# Shock_Clock.net
KiCad netlist of a schematic drawn in EAGLE
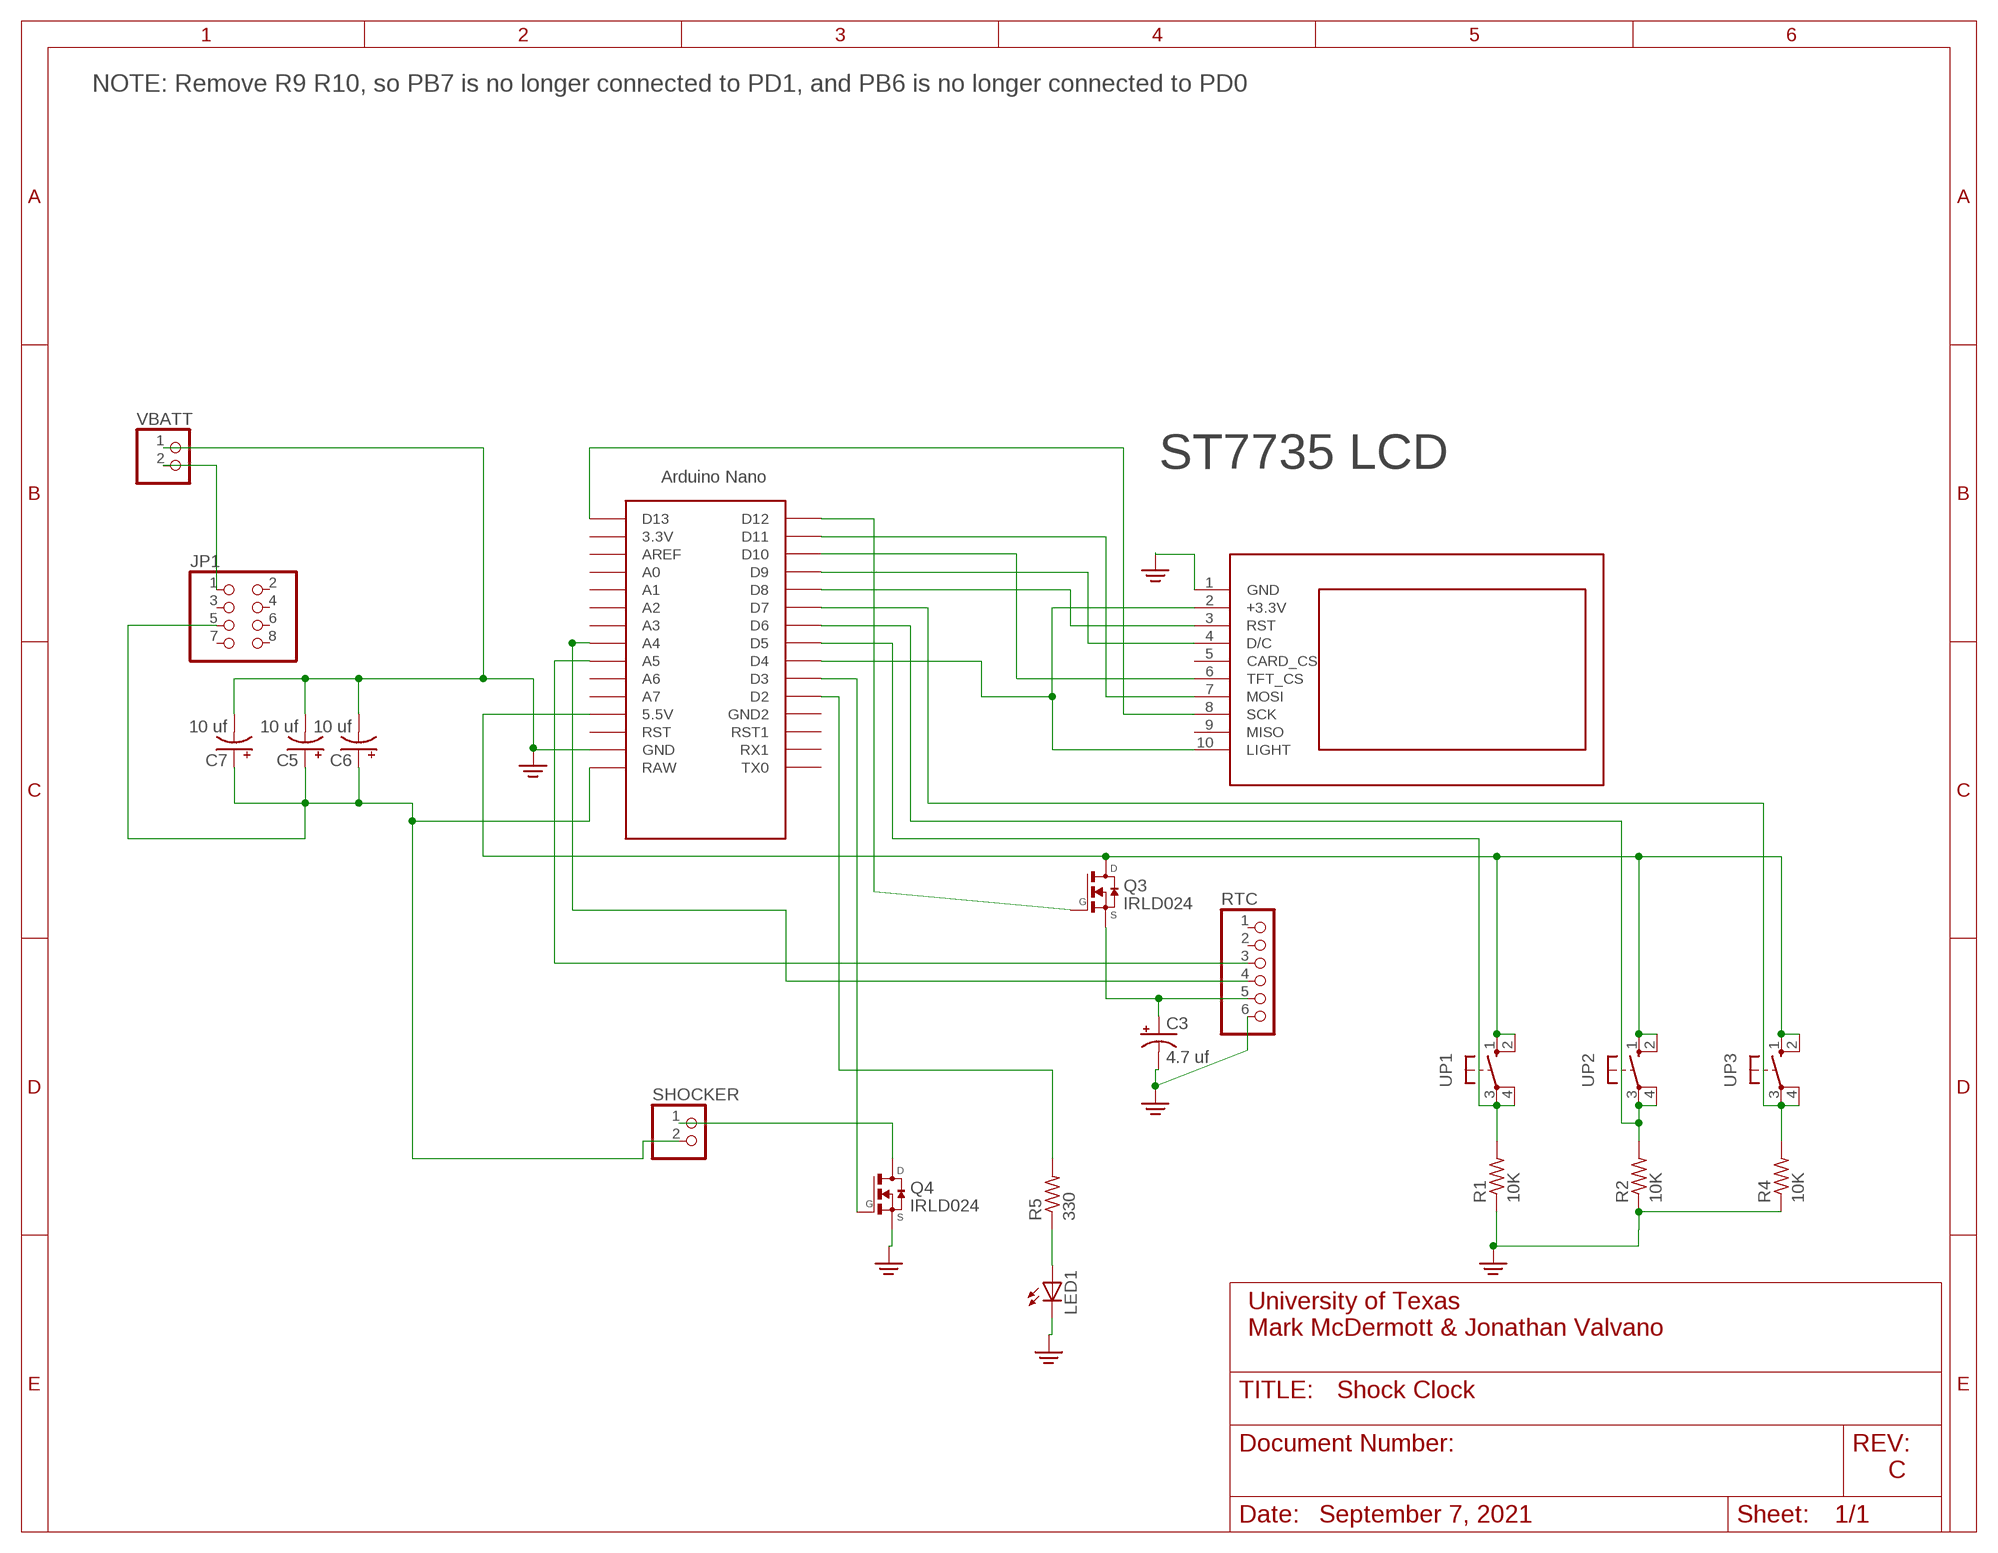
[diagram p0: schematic, sheet 1]

(export (version "E")
  (design (tool "Eeschema 10.0.6"))
  (components
    (comp (ref "C3")
      (value "4.7 uf")
      (footprint "eagle-import:CAP200MILPOLARIZED")
      (libsource (lib "eagle-import") (part "CAPACITOR_POLARIZEDE5-6"))
    )
    (comp (ref "C5")
      (value "10 uf")
      (footprint "eagle-import:CAP200MILPOLARIZED")
      (libsource (lib "eagle-import") (part "CAPACITOR_POLARIZEDE5-6"))
    )
    (comp (ref "C6")
      (value "10 uf")
      (footprint "eagle-import:CAP200MILPOLARIZED")
      (libsource (lib "eagle-import") (part "CAPACITOR_POLARIZEDE5-6"))
    )
    (comp (ref "C7")
      (value "10 uf")
      (footprint "eagle-import:CAP200MILPOLARIZED")
      (libsource (lib "eagle-import") (part "CAPACITOR_POLARIZEDE5-6"))
    )
    (comp (ref "JP1")
      (value "PINHD-2X4")
      (footprint "eagle-import:2X04")
      (libsource (lib "eagle-import") (part "PINHD-2X4"))
    )
    (comp (ref "LED1")
      (value "LED3MM")
      (footprint "eagle-import:LED3MM")
      (libsource (lib "eagle-import") (part "LED3MM"))
    )
    (comp (ref "Q3")
      (value "IRLD024")
      (footprint "eagle-import:IRLD024")
      (libsource (lib "eagle-import") (part "IRLD024"))
    )
    (comp (ref "Q4")
      (value "IRLD024")
      (footprint "eagle-import:IRLD024")
      (libsource (lib "eagle-import") (part "IRLD024"))
    )
    (comp (ref "R1")
      (value "10K")
      (footprint "eagle-import:RES300MIL")
      (libsource (lib "eagle-import") (part "RESISTOR0204/7"))
    )
    (comp (ref "R2")
      (value "10K")
      (footprint "eagle-import:RES300MIL")
      (libsource (lib "eagle-import") (part "RESISTOR0204/7"))
    )
    (comp (ref "R4")
      (value "10K")
      (footprint "eagle-import:RES300MIL")
      (libsource (lib "eagle-import") (part "RESISTOR0204/7"))
    )
    (comp (ref "R5")
      (value "330")
      (footprint "eagle-import:RES300MIL")
      (libsource (lib "eagle-import") (part "RESISTOR0204/7"))
    )
    (comp (ref "RTC")
      (value "PINHD-1X6")
      (footprint "eagle-import:1X06")
      (libsource (lib "eagle-import") (part "PINHD-1X6"))
    )
    (comp (ref "SHOCKER")
      (value "PINHD-1X2")
      (footprint "eagle-import:1X02")
      (libsource (lib "eagle-import") (part "PINHD-1X2"))
    )
    (comp (ref "U$3")
      (value "ST7735")
      (footprint "eagle-import:ST7735")
      (libsource (lib "eagle-import") (part "ST7735"))
    )
    (comp (ref "U$5")
      (value "NANO")
      (footprint "eagle-import:NANO")
      (libsource (lib "eagle-import") (part "NANO"))
    )
    (comp (ref "UP1")
      (value "B3F-1052")
      (footprint "eagle-import:B3F-10XX")
      (fields (field (name "MPN") "B3F-1000"))
      (libsource (lib "eagle-import") (part "B3F-1052"))
    )
    (comp (ref "UP2")
      (value "B3F-1052")
      (footprint "eagle-import:B3F-10XX")
      (fields (field (name "MPN") "B3F-1000"))
      (libsource (lib "eagle-import") (part "B3F-1052"))
    )
    (comp (ref "UP3")
      (value "B3F-1052")
      (footprint "eagle-import:B3F-10XX")
      (fields (field (name "MPN") "B3F-1000"))
      (libsource (lib "eagle-import") (part "B3F-1052"))
    )
    (comp (ref "VBATT")
      (value "PINHD-1X2")
      (footprint "eagle-import:1X02")
      (libsource (lib "eagle-import") (part "PINHD-1X2"))
    )
  )
  (nets
    (net (code "1") (name "GND") (class "Default")
      (node (ref "C3") (pin "-") (pinfunction "-_-") (pintype "passive"))
      (node (ref "C5") (pin "-") (pinfunction "-_-") (pintype "passive"))
      (node (ref "C6") (pin "-") (pinfunction "-_-") (pintype "passive"))
      (node (ref "C7") (pin "-") (pinfunction "-_-") (pintype "passive"))
      (node (ref "LED1") (pin "K") (pinfunction "C_K") (pintype "passive"))
      (node (ref "Q4") (pin "P$4") (pinfunction "S_P$4") (pintype "passive"))
      (node (ref "R1") (pin "1") (pinfunction "1_1") (pintype "passive"))
      (node (ref "R2") (pin "1") (pinfunction "1_1") (pintype "passive"))
      (node (ref "R4") (pin "1") (pinfunction "1_1") (pintype "passive"))
      (node (ref "RTC") (pin "6") (pinfunction "6_6") (pintype "passive"))
      (node (ref "U$3") (pin "1") (pinfunction "GND_1") (pintype "bidirectional"))
      (node (ref "U$5") (pin "GND") (pinfunction "GND_GND") (pintype "bidirectional"))
      (node (ref "VBATT") (pin "1") (pinfunction "1_1") (pintype "passive"))
    )
    (net (code "2") (name "Net-(C5-Pad+)") (class "Default")
      (node (ref "C5") (pin "+") (pinfunction "+_+") (pintype "passive"))
      (node (ref "C6") (pin "+") (pinfunction "+_+") (pintype "passive"))
      (node (ref "C7") (pin "+") (pinfunction "+_+") (pintype "passive"))
      (node (ref "JP1") (pin "5") (pinfunction "5_5") (pintype "passive"))
      (node (ref "SHOCKER") (pin "2") (pinfunction "2_2") (pintype "passive"))
      (node (ref "U$5") (pin "RAW") (pinfunction "RAW_RAW") (pintype "bidirectional"))
    )
    (net (code "3") (name "Net-(JP1-Pad1)") (class "Default")
      (node (ref "JP1") (pin "1") (pinfunction "1_1") (pintype "passive"))
      (node (ref "VBATT") (pin "2") (pinfunction "2_2") (pintype "passive"))
    )
    (net (code "4") (name "Net-(LED1-PadA)") (class "Default")
      (node (ref "LED1") (pin "A") (pinfunction "A_A") (pintype "passive"))
      (node (ref "R5") (pin "1") (pinfunction "1_1") (pintype "passive"))
    )
    (net (code "5") (name "Net-(Q3-D)") (class "Default")
      (node (ref "Q3") (pin "P$1") (pinfunction "D_P$1") (pintype "passive"))
      (node (ref "U$5") (pin "5V") (pinfunction "5.5V_5V") (pintype "bidirectional"))
      (node (ref "UP1") (pin "1") (pinfunction "S_1") (pintype "passive"))
      (node (ref "UP1") (pin "2") (pinfunction "S1_2") (pintype "passive"))
      (node (ref "UP2") (pin "1") (pinfunction "S_1") (pintype "passive"))
      (node (ref "UP2") (pin "2") (pinfunction "S1_2") (pintype "passive"))
      (node (ref "UP3") (pin "1") (pinfunction "S_1") (pintype "passive"))
      (node (ref "UP3") (pin "2") (pinfunction "S1_2") (pintype "passive"))
    )
    (net (code "6") (name "Net-(Q3-G)") (class "Default")
      (node (ref "Q3") (pin "P$3") (pinfunction "G_P$3") (pintype "passive"))
      (node (ref "U$5") (pin "D12") (pinfunction "D12_D12") (pintype "bidirectional"))
    )
    (net (code "7") (name "Net-(Q3-S)") (class "Default")
      (node (ref "C3") (pin "+") (pinfunction "+_+") (pintype "passive"))
      (node (ref "Q3") (pin "P$4") (pinfunction "S_P$4") (pintype "passive"))
      (node (ref "RTC") (pin "5") (pinfunction "5_5") (pintype "passive"))
    )
    (net (code "8") (name "Net-(Q4-D)") (class "Default")
      (node (ref "Q4") (pin "P$1") (pinfunction "D_P$1") (pintype "passive"))
      (node (ref "SHOCKER") (pin "1") (pinfunction "1_1") (pintype "passive"))
    )
    (net (code "9") (name "Net-(Q4-G)") (class "Default")
      (node (ref "Q4") (pin "P$3") (pinfunction "G_P$3") (pintype "passive"))
      (node (ref "U$5") (pin "D3") (pinfunction "D3_D3") (pintype "bidirectional"))
    )
    (net (code "10") (name "Net-(R5-Pad2)") (class "Default")
      (node (ref "R5") (pin "2") (pinfunction "2_2") (pintype "passive"))
      (node (ref "U$5") (pin "D2") (pinfunction "D2_D2") (pintype "bidirectional"))
    )
    (net (code "11") (name "Net-(RTC-Pad3)") (class "Default")
      (node (ref "RTC") (pin "3") (pinfunction "3_3") (pintype "passive"))
      (node (ref "U$5") (pin "A5") (pinfunction "A5_A5") (pintype "bidirectional"))
    )
    (net (code "12") (name "Net-(RTC-Pad4)") (class "Default")
      (node (ref "RTC") (pin "4") (pinfunction "4_4") (pintype "passive"))
      (node (ref "U$5") (pin "A4") (pinfunction "A4_A4") (pintype "bidirectional"))
    )
    (net (code "13") (name "Net-(U$3-+3.3V)") (class "Default")
      (node (ref "U$3") (pin "10") (pinfunction "LIGHT_10") (pintype "bidirectional"))
      (node (ref "U$3") (pin "2") (pinfunction "+3.3V_2") (pintype "bidirectional"))
      (node (ref "U$5") (pin "D4") (pinfunction "D4_D4") (pintype "bidirectional"))
    )
    (net (code "14") (name "Net-(U$3-D{slash}C)") (class "Default")
      (node (ref "U$3") (pin "4") (pinfunction "D/C_4") (pintype "bidirectional"))
      (node (ref "U$5") (pin "D9") (pinfunction "D9_D9") (pintype "bidirectional"))
    )
    (net (code "15") (name "Net-(U$3-MOSI)") (class "Default")
      (node (ref "U$3") (pin "7") (pinfunction "MOSI_7") (pintype "bidirectional"))
      (node (ref "U$5") (pin "D11") (pinfunction "D11_D11") (pintype "bidirectional"))
    )
    (net (code "16") (name "Net-(U$3-RST)") (class "Default")
      (node (ref "U$3") (pin "3") (pinfunction "RST_3") (pintype "bidirectional"))
      (node (ref "U$5") (pin "D8") (pinfunction "D8_D8") (pintype "bidirectional"))
    )
    (net (code "17") (name "Net-(U$3-SCK)") (class "Default")
      (node (ref "U$3") (pin "8") (pinfunction "SCK_8") (pintype "bidirectional"))
      (node (ref "U$5") (pin "D13") (pinfunction "D13_D13") (pintype "bidirectional"))
    )
    (net (code "18") (name "Net-(U$3-TFT_CS)") (class "Default")
      (node (ref "U$3") (pin "6") (pinfunction "TFT_CS_6") (pintype "bidirectional"))
      (node (ref "U$5") (pin "D10") (pinfunction "D10_D10") (pintype "bidirectional"))
    )
    (net (code "19") (name "Net-(UP1-P)") (class "Default")
      (node (ref "R1") (pin "2") (pinfunction "2_2") (pintype "passive"))
      (node (ref "U$5") (pin "D5") (pinfunction "D5_D5") (pintype "bidirectional"))
      (node (ref "UP1") (pin "3") (pinfunction "P_3") (pintype "passive"))
      (node (ref "UP1") (pin "4") (pinfunction "P1_4") (pintype "passive"))
    )
    (net (code "20") (name "Net-(UP2-P)") (class "Default")
      (node (ref "R2") (pin "2") (pinfunction "2_2") (pintype "passive"))
      (node (ref "U$5") (pin "D6") (pinfunction "D6_D6") (pintype "bidirectional"))
      (node (ref "UP2") (pin "3") (pinfunction "P_3") (pintype "passive"))
      (node (ref "UP2") (pin "4") (pinfunction "P1_4") (pintype "passive"))
    )
    (net (code "21") (name "Net-(UP3-P)") (class "Default")
      (node (ref "R4") (pin "2") (pinfunction "2_2") (pintype "passive"))
      (node (ref "U$5") (pin "D7") (pinfunction "D7_D7") (pintype "bidirectional"))
      (node (ref "UP3") (pin "3") (pinfunction "P_3") (pintype "passive"))
      (node (ref "UP3") (pin "4") (pinfunction "P1_4") (pintype "passive"))
    )
    (net (code "22") (name "unconnected-(JP1-Pad2)") (class "Default")
      (node (ref "JP1") (pin "2") (pinfunction "2_2") (pintype "passive"))
    )
    (net (code "23") (name "unconnected-(JP1-Pad3)") (class "Default")
      (node (ref "JP1") (pin "3") (pinfunction "3_3") (pintype "passive"))
    )
    (net (code "24") (name "unconnected-(JP1-Pad4)") (class "Default")
      (node (ref "JP1") (pin "4") (pinfunction "4_4") (pintype "passive"))
    )
    (net (code "25") (name "unconnected-(JP1-Pad6)") (class "Default")
      (node (ref "JP1") (pin "6") (pinfunction "6_6") (pintype "passive"))
    )
    (net (code "26") (name "unconnected-(JP1-Pad7)") (class "Default")
      (node (ref "JP1") (pin "7") (pinfunction "7_7") (pintype "passive"))
    )
    (net (code "27") (name "unconnected-(JP1-Pad8)") (class "Default")
      (node (ref "JP1") (pin "8") (pinfunction "8_8") (pintype "passive"))
    )
    (net (code "28") (name "unconnected-(RTC-Pad1)") (class "Default")
      (node (ref "RTC") (pin "1") (pinfunction "1_1") (pintype "passive"))
    )
    (net (code "29") (name "unconnected-(RTC-Pad2)") (class "Default")
      (node (ref "RTC") (pin "2") (pinfunction "2_2") (pintype "passive"))
    )
    (net (code "30") (name "unconnected-(U$3-CARD_CS-Pad5)") (class "Default")
      (node (ref "U$3") (pin "5") (pinfunction "CARD_CS_5") (pintype "bidirectional"))
    )
    (net (code "31") (name "unconnected-(U$3-MISO-Pad9)") (class "Default")
      (node (ref "U$3") (pin "9") (pinfunction "MISO_9") (pintype "bidirectional"))
    )
    (net (code "32") (name "unconnected-(U$5-GND2-PadGND1)") (class "Default")
      (node (ref "U$5") (pin "GND1") (pinfunction "GND2_GND1") (pintype "bidirectional"))
    )
    (net (code "33") (name "unconnected-(U$5-Pad3.3V)") (class "Default")
      (node (ref "U$5") (pin "3.3V") (pinfunction "3.3V_3.3V") (pintype "bidirectional"))
    )
    (net (code "34") (name "unconnected-(U$5-PadA0)") (class "Default")
      (node (ref "U$5") (pin "A0") (pinfunction "A0_A0") (pintype "bidirectional"))
    )
    (net (code "35") (name "unconnected-(U$5-PadA1)") (class "Default")
      (node (ref "U$5") (pin "A1") (pinfunction "A1_A1") (pintype "bidirectional"))
    )
    (net (code "36") (name "unconnected-(U$5-PadA2)") (class "Default")
      (node (ref "U$5") (pin "A2") (pinfunction "A2_A2") (pintype "bidirectional"))
    )
    (net (code "37") (name "unconnected-(U$5-PadA3)") (class "Default")
      (node (ref "U$5") (pin "A3") (pinfunction "A3_A3") (pintype "bidirectional"))
    )
    (net (code "38") (name "unconnected-(U$5-PadA6)") (class "Default")
      (node (ref "U$5") (pin "A6") (pinfunction "A6_A6") (pintype "bidirectional"))
    )
    (net (code "39") (name "unconnected-(U$5-PadA7)") (class "Default")
      (node (ref "U$5") (pin "A7") (pinfunction "A7_A7") (pintype "bidirectional"))
    )
    (net (code "40") (name "unconnected-(U$5-PadAREF)") (class "Default")
      (node (ref "U$5") (pin "AREF") (pinfunction "AREF_AREF") (pintype "bidirectional"))
    )
    (net (code "41") (name "unconnected-(U$5-PadICSP1)") (class "Default")
      (node (ref "U$5") (pin "ICSP1") (pinfunction "ICSP1_ICSP1") (pintype "bidirectional"))
    )
    (net (code "42") (name "unconnected-(U$5-PadICSP2)") (class "Default")
      (node (ref "U$5") (pin "ICSP2") (pinfunction "ICSP2_ICSP2") (pintype "bidirectional"))
    )
    (net (code "43") (name "unconnected-(U$5-PadICSP3)") (class "Default")
      (node (ref "U$5") (pin "ICSP3") (pinfunction "ICSP3_ICSP3") (pintype "bidirectional"))
    )
    (net (code "44") (name "unconnected-(U$5-PadICSP4)") (class "Default")
      (node (ref "U$5") (pin "ICSP4") (pinfunction "ICSP4_ICSP4") (pintype "bidirectional"))
    )
    (net (code "45") (name "unconnected-(U$5-PadICSP5)") (class "Default")
      (node (ref "U$5") (pin "ICSP5") (pinfunction "ICSP5_ICSP5") (pintype "bidirectional"))
    )
    (net (code "46") (name "unconnected-(U$5-PadICSP6)") (class "Default")
      (node (ref "U$5") (pin "ICSP6") (pinfunction "ICSP6_ICSP6") (pintype "bidirectional"))
    )
    (net (code "47") (name "unconnected-(U$5-PadRST)") (class "Default")
      (node (ref "U$5") (pin "RST") (pinfunction "RST_RST") (pintype "bidirectional"))
    )
    (net (code "48") (name "unconnected-(U$5-PadRST1)") (class "Default")
      (node (ref "U$5") (pin "RST1") (pinfunction "RST1_RST1") (pintype "bidirectional"))
    )
    (net (code "49") (name "unconnected-(U$5-PadRX1)") (class "Default")
      (node (ref "U$5") (pin "RX1") (pinfunction "RX1_RX1") (pintype "bidirectional"))
    )
    (net (code "50") (name "unconnected-(U$5-PadTX0)") (class "Default")
      (node (ref "U$5") (pin "TX0") (pinfunction "TX0_TX0") (pintype "bidirectional"))
    )
  )
)
